# 130807_AriloRX_FINAL_LOGO.net
KiCad netlist of a schematic drawn in EAGLE
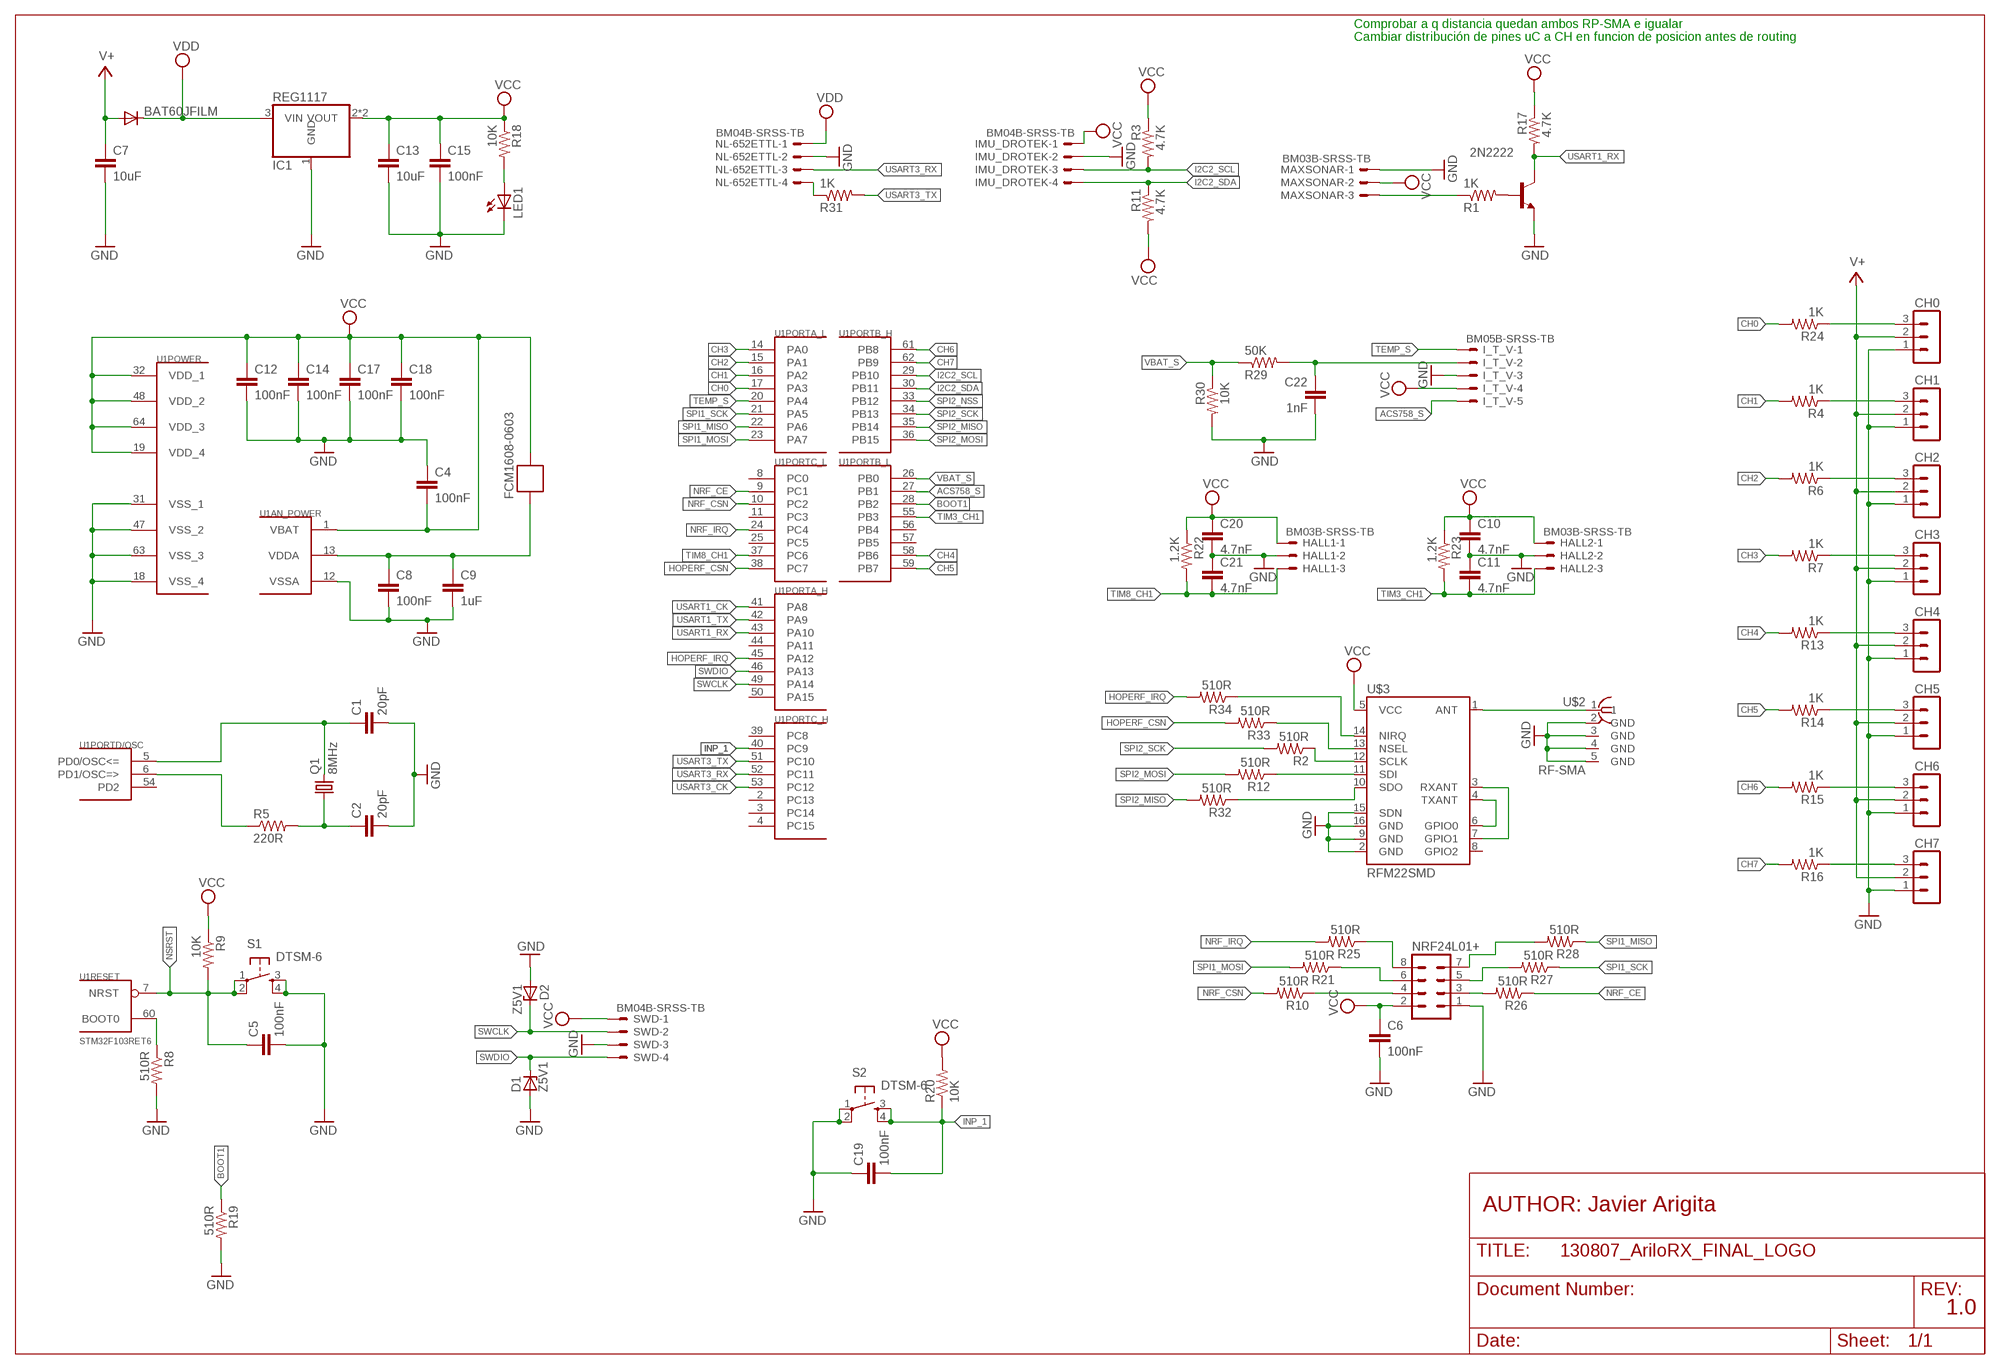
[diagram p0: schematic, sheet 1]

(export (version "E")
  (design (tool "Eeschema 10.0.6"))
  (components
    (comp (ref "2N2222")
      (value "MMBT2222ALT1-NPN-SOT23-BEC")
      (footprint "eagle-import:SOT23-BEC")
      (libsource (lib "eagle-import") (part "-NPN-SOT23-BECMMBT2222ALT1"))
    )
    (comp (ref "BAT60JFILM")
      (value "DIODE-SOD323-R")
      (footprint "eagle-import:SOD323-R")
      (libsource (lib "eagle-import") (part "DIODE-SOD323-R"))
    )
    (comp (ref "C1")
      (value "20pF")
      (footprint "eagle-import:C0805")
      (libsource (lib "eagle-import") (part "C-EUC0805"))
    )
    (comp (ref "C2")
      (value "20pF")
      (footprint "eagle-import:C0805")
      (libsource (lib "eagle-import") (part "C-EUC0805"))
    )
    (comp (ref "C4")
      (value "100nF")
      (footprint "eagle-import:C0805")
      (libsource (lib "eagle-import") (part "C-EUC0805"))
    )
    (comp (ref "C5")
      (value "100nF")
      (footprint "eagle-import:C0805")
      (libsource (lib "eagle-import") (part "C-EUC0805"))
    )
    (comp (ref "C6")
      (value "100nF")
      (footprint "eagle-import:C0805")
      (libsource (lib "eagle-import") (part "C-EUC0805"))
    )
    (comp (ref "C7")
      (value "10uF")
      (footprint "eagle-import:C3216")
      (libsource (lib "eagle-import") (part "resistor_C-EUC3216"))
    )
    (comp (ref "C8")
      (value "100nF")
      (footprint "eagle-import:C0805")
      (libsource (lib "eagle-import") (part "C-EUC0805"))
    )
    (comp (ref "C9")
      (value "1uF")
      (footprint "eagle-import:C3216")
      (libsource (lib "eagle-import") (part "resistor_C-EUC3216"))
    )
    (comp (ref "C10")
      (value "4.7nF")
      (footprint "eagle-import:C0805")
      (libsource (lib "eagle-import") (part "C-EUC0805"))
    )
    (comp (ref "C11")
      (value "4.7nF")
      (footprint "eagle-import:C0805")
      (libsource (lib "eagle-import") (part "C-EUC0805"))
    )
    (comp (ref "C12")
      (value "100nF")
      (footprint "eagle-import:C0805")
      (libsource (lib "eagle-import") (part "C-EUC0805"))
    )
    (comp (ref "C13")
      (value "10uF")
      (footprint "eagle-import:C3216")
      (libsource (lib "eagle-import") (part "resistor_C-EUC3216"))
    )
    (comp (ref "C14")
      (value "100nF")
      (footprint "eagle-import:C0805")
      (libsource (lib "eagle-import") (part "C-EUC0805"))
    )
    (comp (ref "C15")
      (value "100nF")
      (footprint "eagle-import:C0805")
      (libsource (lib "eagle-import") (part "C-EUC0805"))
    )
    (comp (ref "C17")
      (value "100nF")
      (footprint "eagle-import:C0805")
      (libsource (lib "eagle-import") (part "C-EUC0805"))
    )
    (comp (ref "C18")
      (value "100nF")
      (footprint "eagle-import:C0805")
      (libsource (lib "eagle-import") (part "C-EUC0805"))
    )
    (comp (ref "C19")
      (value "100nF")
      (footprint "eagle-import:C0805")
      (libsource (lib "eagle-import") (part "C-EUC0805"))
    )
    (comp (ref "C20")
      (value "4.7nF")
      (footprint "eagle-import:C0805")
      (libsource (lib "eagle-import") (part "C-EUC0805"))
    )
    (comp (ref "C21")
      (value "4.7nF")
      (footprint "eagle-import:C0805")
      (libsource (lib "eagle-import") (part "C-EUC0805"))
    )
    (comp (ref "C22")
      (value "1nF")
      (footprint "eagle-import:C0805")
      (libsource (lib "eagle-import") (part "C-EUC0805"))
    )
    (comp (ref "CH0")
      (value "MA03-1")
      (footprint "eagle-import:MA03-1")
      (libsource (lib "eagle-import") (part "MA03-1"))
    )
    (comp (ref "CH1")
      (value "MA03-1")
      (footprint "eagle-import:MA03-1")
      (libsource (lib "eagle-import") (part "MA03-1"))
    )
    (comp (ref "CH2")
      (value "MA03-1")
      (footprint "eagle-import:MA03-1")
      (libsource (lib "eagle-import") (part "MA03-1"))
    )
    (comp (ref "CH3")
      (value "MA03-1")
      (footprint "eagle-import:MA03-1")
      (libsource (lib "eagle-import") (part "MA03-1"))
    )
    (comp (ref "CH4")
      (value "MA03-1")
      (footprint "eagle-import:MA03-1")
      (libsource (lib "eagle-import") (part "MA03-1"))
    )
    (comp (ref "CH5")
      (value "MA03-1")
      (footprint "eagle-import:MA03-1")
      (libsource (lib "eagle-import") (part "MA03-1"))
    )
    (comp (ref "CH6")
      (value "MA03-1")
      (footprint "eagle-import:MA03-1")
      (libsource (lib "eagle-import") (part "MA03-1"))
    )
    (comp (ref "CH7")
      (value "MA03-1")
      (footprint "eagle-import:MA03-1")
      (libsource (lib "eagle-import") (part "MA03-1"))
    )
    (comp (ref "D1")
      (value "Z5V1")
      (footprint "eagle-import:SOD80C")
      (libsource (lib "eagle-import") (part "ZENER-DIODESOD80C"))
    )
    (comp (ref "D2")
      (value "Z5V1")
      (footprint "eagle-import:SOD80C")
      (libsource (lib "eagle-import") (part "ZENER-DIODESOD80C"))
    )
    (comp (ref "FCM1608-0603")
      (value "FERRITE-BEAD")
      (footprint "eagle-import:R0603")
      (libsource (lib "eagle-import") (part "FERRITE-BEAD"))
    )
    (comp (ref "HALL1")
      (value "BM03B-SRSS-TB")
      (footprint "eagle-import:BM03B-SRSS-TB")
      (libsource (lib "eagle-import") (part "?M03B-SRSS-TBB"))
    )
    (comp (ref "HALL2")
      (value "BM03B-SRSS-TB")
      (footprint "eagle-import:BM03B-SRSS-TB")
      (libsource (lib "eagle-import") (part "?M03B-SRSS-TBB"))
    )
    (comp (ref "IC1")
      (value "REG1117")
      (footprint "eagle-import:SOT223")
      (libsource (lib "eagle-import") (part "REG1117"))
    )
    (comp (ref "IMU_DROTEK")
      (value "BM04B-SRSS-TB")
      (footprint "eagle-import:BM04B-SRSS-TB")
      (libsource (lib "eagle-import") (part "?M04B-SRSS-TBB"))
    )
    (comp (ref "I_T_V")
      (value "BM05B-SRSS-TB")
      (footprint "eagle-import:BM05B-SRSS-TB")
      (libsource (lib "eagle-import") (part "?M05B-SRSS-TBB"))
    )
    (comp (ref "LED1")
      (value "LED0805")
      (footprint "eagle-import:CHIPLED_0805")
      (libsource (lib "eagle-import") (part "LED0805"))
    )
    (comp (ref "MAXSONAR")
      (value "BM03B-SRSS-TB")
      (footprint "eagle-import:BM03B-SRSS-TB")
      (libsource (lib "eagle-import") (part "?M03B-SRSS-TBB"))
    )
    (comp (ref "NL-652ETTL")
      (value "BM04B-SRSS-TB")
      (footprint "eagle-import:BM04B-SRSS-TB")
      (libsource (lib "eagle-import") (part "?M04B-SRSS-TBB"))
    )
    (comp (ref "NRF24L01+")
      (value "MA04-2")
      (footprint "eagle-import:MA04-2")
      (libsource (lib "eagle-import") (part "MA04-2"))
    )
    (comp (ref "Q1")
      (value "8MHz")
      (footprint "eagle-import:SM49")
      (libsource (lib "eagle-import") (part "CRYSTALSM49"))
    )
    (comp (ref "R1")
      (value "1K")
      (footprint "eagle-import:R0805")
      (libsource (lib "eagle-import") (part "RESISTOR0805"))
    )
    (comp (ref "R2")
      (value "510R")
      (footprint "eagle-import:R0805")
      (libsource (lib "eagle-import") (part "RESISTOR0805"))
    )
    (comp (ref "R3")
      (value "4.7K")
      (footprint "eagle-import:R0805")
      (libsource (lib "eagle-import") (part "RESISTOR0805"))
    )
    (comp (ref "R4")
      (value "1K")
      (footprint "eagle-import:R0805")
      (libsource (lib "eagle-import") (part "RESISTOR0805"))
    )
    (comp (ref "R5")
      (value "220R")
      (footprint "eagle-import:R0805")
      (libsource (lib "eagle-import") (part "RESISTOR0805"))
    )
    (comp (ref "R6")
      (value "1K")
      (footprint "eagle-import:R0805")
      (libsource (lib "eagle-import") (part "RESISTOR0805"))
    )
    (comp (ref "R7")
      (value "1K")
      (footprint "eagle-import:R0805")
      (libsource (lib "eagle-import") (part "RESISTOR0805"))
    )
    (comp (ref "R8")
      (value "510R")
      (footprint "eagle-import:R0805")
      (libsource (lib "eagle-import") (part "RESISTOR0805"))
    )
    (comp (ref "R9")
      (value "10K")
      (footprint "eagle-import:R0805")
      (libsource (lib "eagle-import") (part "RESISTOR0805"))
    )
    (comp (ref "R10")
      (value "510R")
      (footprint "eagle-import:R0805")
      (libsource (lib "eagle-import") (part "RESISTOR0805"))
    )
    (comp (ref "R11")
      (value "4.7K")
      (footprint "eagle-import:R0805")
      (libsource (lib "eagle-import") (part "RESISTOR0805"))
    )
    (comp (ref "R12")
      (value "510R")
      (footprint "eagle-import:R0805")
      (libsource (lib "eagle-import") (part "RESISTOR0805"))
    )
    (comp (ref "R13")
      (value "1K")
      (footprint "eagle-import:R0805")
      (libsource (lib "eagle-import") (part "RESISTOR0805"))
    )
    (comp (ref "R14")
      (value "1K")
      (footprint "eagle-import:R0805")
      (libsource (lib "eagle-import") (part "RESISTOR0805"))
    )
    (comp (ref "R15")
      (value "1K")
      (footprint "eagle-import:R0805")
      (libsource (lib "eagle-import") (part "RESISTOR0805"))
    )
    (comp (ref "R16")
      (value "1K")
      (footprint "eagle-import:R0805")
      (libsource (lib "eagle-import") (part "RESISTOR0805"))
    )
    (comp (ref "R17")
      (value "4.7K")
      (footprint "eagle-import:R0805")
      (libsource (lib "eagle-import") (part "RESISTOR0805"))
    )
    (comp (ref "R18")
      (value "10K")
      (footprint "eagle-import:R0805")
      (libsource (lib "eagle-import") (part "RESISTOR0805"))
    )
    (comp (ref "R19")
      (value "510R")
      (footprint "eagle-import:R0805")
      (libsource (lib "eagle-import") (part "RESISTOR0805"))
    )
    (comp (ref "R20")
      (value "10K")
      (footprint "eagle-import:R0805")
      (libsource (lib "eagle-import") (part "RESISTOR0805"))
    )
    (comp (ref "R21")
      (value "510R")
      (footprint "eagle-import:R0805")
      (libsource (lib "eagle-import") (part "RESISTOR0805"))
    )
    (comp (ref "R22")
      (value "1.2K")
      (footprint "eagle-import:R0805")
      (libsource (lib "eagle-import") (part "RESISTOR0805"))
    )
    (comp (ref "R23")
      (value "1.2K")
      (footprint "eagle-import:R0805")
      (libsource (lib "eagle-import") (part "RESISTOR0805"))
    )
    (comp (ref "R24")
      (value "1K")
      (footprint "eagle-import:R0805")
      (libsource (lib "eagle-import") (part "RESISTOR0805"))
    )
    (comp (ref "R25")
      (value "510R")
      (footprint "eagle-import:R0805")
      (libsource (lib "eagle-import") (part "RESISTOR0805"))
    )
    (comp (ref "R26")
      (value "510R")
      (footprint "eagle-import:R0805")
      (libsource (lib "eagle-import") (part "RESISTOR0805"))
    )
    (comp (ref "R27")
      (value "510R")
      (footprint "eagle-import:R0805")
      (libsource (lib "eagle-import") (part "RESISTOR0805"))
    )
    (comp (ref "R28")
      (value "510R")
      (footprint "eagle-import:R0805")
      (libsource (lib "eagle-import") (part "RESISTOR0805"))
    )
    (comp (ref "R29")
      (value "50K")
      (footprint "eagle-import:R0805")
      (libsource (lib "eagle-import") (part "RESISTOR0805"))
    )
    (comp (ref "R30")
      (value "10K")
      (footprint "eagle-import:R0805")
      (libsource (lib "eagle-import") (part "RESISTOR0805"))
    )
    (comp (ref "R31")
      (value "1K")
      (footprint "eagle-import:R0805")
      (libsource (lib "eagle-import") (part "RESISTOR0805"))
    )
    (comp (ref "R32")
      (value "510R")
      (footprint "eagle-import:R0805")
      (libsource (lib "eagle-import") (part "RESISTOR0805"))
    )
    (comp (ref "R33")
      (value "510R")
      (footprint "eagle-import:R0805")
      (libsource (lib "eagle-import") (part "RESISTOR0805"))
    )
    (comp (ref "R34")
      (value "510R")
      (footprint "eagle-import:R0805")
      (libsource (lib "eagle-import") (part "RESISTOR0805"))
    )
    (comp (ref "S1")
      (value "DTSM-6")
      (footprint "eagle-import:DTSM-6")
      (libsource (lib "eagle-import") (part "DTSM-6"))
    )
    (comp (ref "S2")
      (value "DTSM-6")
      (footprint "eagle-import:DTSM-6")
      (libsource (lib "eagle-import") (part "DTSM-6"))
    )
    (comp (ref "SWD")
      (value "BM04B-SRSS-TB")
      (footprint "eagle-import:BM04B-SRSS-TB")
      (libsource (lib "eagle-import") (part "?M04B-SRSS-TBB"))
    )
    (comp (ref "U$2")
      (value "RF-SMA")
      (footprint "eagle-import:BU-SMA-H")
      (libsource (lib "eagle-import") (part "RF-SMA"))
    )
    (comp (ref "U$3")
      (value "RFM22SMD")
      (footprint "eagle-import:RFM22-XXX-S2")
      (libsource (lib "eagle-import") (part "RFM22SMD"))
    )
    (comp (ref "U1")
      (value "STM32F103RET6")
      (footprint "eagle-import:TQFP64")
      (libsource (lib "eagle-import") (part "STM32F10XRXT6"))
    )
  )
  (nets
    (net (code "1") (name "ACS758_S") (class "Default")
      (node (ref "I_T_V") (pin "5") (pinfunction "S_5") (pintype "passive"))
      (node (ref "U1") (pin "27") (pinfunction "PB1_27") (pintype "bidirectional"))
    )
    (net (code "2") (name "BOOT1") (class "Default")
      (node (ref "R19") (pin "1") (pinfunction "1_1") (pintype "passive"))
      (node (ref "U1") (pin "28") (pinfunction "PB2_28") (pintype "bidirectional"))
    )
    (net (code "3") (name "CH0") (class "Default")
      (node (ref "R24") (pin "2") (pinfunction "2_2") (pintype "passive"))
      (node (ref "U1") (pin "17") (pinfunction "PA3_17") (pintype "bidirectional"))
    )
    (net (code "4") (name "CH1") (class "Default")
      (node (ref "R4") (pin "2") (pinfunction "2_2") (pintype "passive"))
      (node (ref "U1") (pin "16") (pinfunction "PA2_16") (pintype "bidirectional"))
    )
    (net (code "5") (name "CH2") (class "Default")
      (node (ref "R6") (pin "2") (pinfunction "2_2") (pintype "passive"))
      (node (ref "U1") (pin "15") (pinfunction "PA1_15") (pintype "bidirectional"))
    )
    (net (code "6") (name "CH3") (class "Default")
      (node (ref "R7") (pin "2") (pinfunction "2_2") (pintype "passive"))
      (node (ref "U1") (pin "14") (pinfunction "PA0_14") (pintype "bidirectional"))
    )
    (net (code "7") (name "CH4") (class "Default")
      (node (ref "R13") (pin "2") (pinfunction "2_2") (pintype "passive"))
      (node (ref "U1") (pin "58") (pinfunction "PB6_58") (pintype "bidirectional"))
    )
    (net (code "8") (name "CH5") (class "Default")
      (node (ref "R14") (pin "2") (pinfunction "2_2") (pintype "passive"))
      (node (ref "U1") (pin "59") (pinfunction "PB7_59") (pintype "bidirectional"))
    )
    (net (code "9") (name "CH6") (class "Default")
      (node (ref "R15") (pin "2") (pinfunction "2_2") (pintype "passive"))
      (node (ref "U1") (pin "61") (pinfunction "PB8_61") (pintype "bidirectional"))
    )
    (net (code "10") (name "CH7") (class "Default")
      (node (ref "R16") (pin "2") (pinfunction "2_2") (pintype "passive"))
      (node (ref "U1") (pin "62") (pinfunction "PB9_62") (pintype "bidirectional"))
    )
    (net (code "11") (name "GND") (class "Default")
      (node (ref "2N2222") (pin "E") (pinfunction "E_E") (pintype "passive"))
      (node (ref "C1") (pin "2") (pinfunction "2_2") (pintype "passive"))
      (node (ref "C10") (pin "2") (pinfunction "2_2") (pintype "passive"))
      (node (ref "C11") (pin "1") (pinfunction "1_1") (pintype "passive"))
      (node (ref "C12") (pin "2") (pinfunction "2_2") (pintype "passive"))
      (node (ref "C13") (pin "2") (pinfunction "2_2") (pintype "passive"))
      (node (ref "C14") (pin "2") (pinfunction "2_2") (pintype "passive"))
      (node (ref "C15") (pin "2") (pinfunction "2_2") (pintype "passive"))
      (node (ref "C17") (pin "2") (pinfunction "2_2") (pintype "passive"))
      (node (ref "C18") (pin "2") (pinfunction "2_2") (pintype "passive"))
      (node (ref "C19") (pin "1") (pinfunction "1_1") (pintype "passive"))
      (node (ref "C2") (pin "2") (pinfunction "2_2") (pintype "passive"))
      (node (ref "C20") (pin "2") (pinfunction "2_2") (pintype "passive"))
      (node (ref "C21") (pin "1") (pinfunction "1_1") (pintype "passive"))
      (node (ref "C22") (pin "2") (pinfunction "2_2") (pintype "passive"))
      (node (ref "C4") (pin "1") (pinfunction "1_1") (pintype "passive"))
      (node (ref "C5") (pin "2") (pinfunction "2_2") (pintype "passive"))
      (node (ref "C6") (pin "2") (pinfunction "2_2") (pintype "passive"))
      (node (ref "C7") (pin "2") (pinfunction "2_2") (pintype "passive"))
      (node (ref "C8") (pin "2") (pinfunction "2_2") (pintype "passive"))
      (node (ref "C9") (pin "2") (pinfunction "2_2") (pintype "passive"))
      (node (ref "CH0") (pin "1") (pinfunction "1_1") (pintype "passive"))
      (node (ref "CH1") (pin "1") (pinfunction "1_1") (pintype "passive"))
      (node (ref "CH2") (pin "1") (pinfunction "1_1") (pintype "passive"))
      (node (ref "CH3") (pin "1") (pinfunction "1_1") (pintype "passive"))
      (node (ref "CH4") (pin "1") (pinfunction "1_1") (pintype "passive"))
      (node (ref "CH5") (pin "1") (pinfunction "1_1") (pintype "passive"))
      (node (ref "CH6") (pin "1") (pinfunction "1_1") (pintype "passive"))
      (node (ref "CH7") (pin "1") (pinfunction "1_1") (pintype "passive"))
      (node (ref "D1") (pin "A") (pinfunction "A_A") (pintype "passive"))
      (node (ref "D2") (pin "A") (pinfunction "A_A") (pintype "passive"))
      (node (ref "HALL1") (pin "2") (pinfunction "S_2") (pintype "passive"))
      (node (ref "HALL2") (pin "2") (pinfunction "S_2") (pintype "passive"))
      (node (ref "IC1") (pin "1") (pinfunction "GND_1") (pintype "power_in"))
      (node (ref "IMU_DROTEK") (pin "2") (pinfunction "S_2") (pintype "passive"))
      (node (ref "I_T_V") (pin "3") (pinfunction "S_3") (pintype "passive"))
      (node (ref "LED1") (pin "C") (pinfunction "C_C") (pintype "passive"))
      (node (ref "MAXSONAR") (pin "1") (pinfunction "S_1") (pintype "passive"))
      (node (ref "NL-652ETTL") (pin "2") (pinfunction "S_2") (pintype "passive"))
      (node (ref "NRF24L01+") (pin "1") (pinfunction "1_1") (pintype "passive"))
      (node (ref "R19") (pin "2") (pinfunction "2_2") (pintype "passive"))
      (node (ref "R30") (pin "2") (pinfunction "2_2") (pintype "passive"))
      (node (ref "R8") (pin "2") (pinfunction "2_2") (pintype "passive"))
      (node (ref "S1") (pin "3") (pinfunction "3_3") (pintype "passive"))
      (node (ref "S1") (pin "4") (pinfunction "4_4") (pintype "passive"))
      (node (ref "S2") (pin "1") (pinfunction "1_1") (pintype "passive"))
      (node (ref "S2") (pin "2") (pinfunction "2_2") (pintype "passive"))
      (node (ref "SWD") (pin "3") (pinfunction "S_3") (pintype "passive"))
      (node (ref "U$2") (pin "2") (pinfunction "GND_2") (pintype "power_in"))
      (node (ref "U$2") (pin "3") (pinfunction "GND_3") (pintype "bidirectional"))
      (node (ref "U$2") (pin "4") (pinfunction "GND_4") (pintype "bidirectional"))
      (node (ref "U$2") (pin "5") (pinfunction "GND_5") (pintype "bidirectional"))
      (node (ref "U$3") (pin "15") (pinfunction "SDN_15") (pintype "input"))
      (node (ref "U$3") (pin "16") (pinfunction "GND_16") (pintype "power_in"))
      (node (ref "U$3") (pin "2") (pinfunction "GND_2") (pintype "power_in"))
      (node (ref "U$3") (pin "9") (pinfunction "GND_9") (pintype "power_in"))
      (node (ref "U1") (pin "12") (pinfunction "VSSA_12") (pintype "power_in"))
      (node (ref "U1") (pin "18") (pinfunction "VSS_4_18") (pintype "power_in"))
      (node (ref "U1") (pin "31") (pinfunction "VSS_1_31") (pintype "power_in"))
      (node (ref "U1") (pin "47") (pinfunction "VSS_2_47") (pintype "power_in"))
      (node (ref "U1") (pin "63") (pinfunction "VSS_3_63") (pintype "power_in"))
    )
    (net (code "12") (name "HOPERF_CSN") (class "Default")
      (node (ref "R33") (pin "2") (pinfunction "2_2") (pintype "passive"))
      (node (ref "U1") (pin "38") (pinfunction "PC7_38") (pintype "bidirectional"))
    )
    (net (code "13") (name "HOPERF_IRQ") (class "Default")
      (node (ref "R34") (pin "2") (pinfunction "2_2") (pintype "passive"))
      (node (ref "U1") (pin "45") (pinfunction "PA12_45") (pintype "bidirectional"))
    )
    (net (code "14") (name "I2C2_SCL") (class "Default")
      (node (ref "IMU_DROTEK") (pin "3") (pinfunction "S_3") (pintype "passive"))
      (node (ref "R3") (pin "2") (pinfunction "2_2") (pintype "passive"))
      (node (ref "U1") (pin "29") (pinfunction "PB10_29") (pintype "bidirectional"))
    )
    (net (code "15") (name "I2C2_SDA") (class "Default")
      (node (ref "IMU_DROTEK") (pin "4") (pinfunction "S_4") (pintype "passive"))
      (node (ref "R11") (pin "1") (pinfunction "1_1") (pintype "passive"))
      (node (ref "U1") (pin "30") (pinfunction "PB11_30") (pintype "bidirectional"))
    )
    (net (code "16") (name "INP_1") (class "Default")
      (node (ref "C19") (pin "2") (pinfunction "2_2") (pintype "passive"))
      (node (ref "R20") (pin "1") (pinfunction "1_1") (pintype "passive"))
      (node (ref "S2") (pin "3") (pinfunction "3_3") (pintype "passive"))
      (node (ref "S2") (pin "4") (pinfunction "4_4") (pintype "passive"))
      (node (ref "U1") (pin "40") (pinfunction "PC9_40") (pintype "bidirectional"))
    )
    (net (code "17") (name "NRF_CE") (class "Default")
      (node (ref "R26") (pin "1") (pinfunction "1_1") (pintype "passive"))
      (node (ref "U1") (pin "9") (pinfunction "PC1_9") (pintype "bidirectional"))
    )
    (net (code "18") (name "NRF_CSN") (class "Default")
      (node (ref "R10") (pin "2") (pinfunction "2_2") (pintype "passive"))
      (node (ref "U1") (pin "10") (pinfunction "PC2_10") (pintype "bidirectional"))
    )
    (net (code "19") (name "NRF_IRQ") (class "Default")
      (node (ref "R25") (pin "2") (pinfunction "2_2") (pintype "passive"))
      (node (ref "U1") (pin "24") (pinfunction "PC4_24") (pintype "bidirectional"))
    )
    (net (code "20") (name "NSRST") (class "Default")
      (node (ref "C5") (pin "1") (pinfunction "1_1") (pintype "passive"))
      (node (ref "R9") (pin "2") (pinfunction "2_2") (pintype "passive"))
      (node (ref "S1") (pin "1") (pinfunction "1_1") (pintype "passive"))
      (node (ref "S1") (pin "2") (pinfunction "2_2") (pintype "passive"))
      (node (ref "U1") (pin "7") (pinfunction "NRST_7") (pintype "input"))
    )
    (net (code "21") (name "Net-(2N2222-PadB)") (class "Default")
      (node (ref "2N2222") (pin "B") (pinfunction "B_B") (pintype "passive"))
      (node (ref "R1") (pin "2") (pinfunction "2_2") (pintype "passive"))
    )
    (net (code "22") (name "Net-(C2-Pad1)") (class "Default")
      (node (ref "C2") (pin "1") (pinfunction "1_1") (pintype "passive"))
      (node (ref "Q1") (pin "1") (pinfunction "1_1") (pintype "passive"))
      (node (ref "R5") (pin "2") (pinfunction "2_2") (pintype "passive"))
    )
    (net (code "23") (name "Net-(CH0-Pad3)") (class "Default")
      (node (ref "CH0") (pin "3") (pinfunction "3_3") (pintype "passive"))
      (node (ref "R24") (pin "1") (pinfunction "1_1") (pintype "passive"))
    )
    (net (code "24") (name "Net-(CH1-Pad3)") (class "Default")
      (node (ref "CH1") (pin "3") (pinfunction "3_3") (pintype "passive"))
      (node (ref "R4") (pin "1") (pinfunction "1_1") (pintype "passive"))
    )
    (net (code "25") (name "Net-(CH2-Pad3)") (class "Default")
      (node (ref "CH2") (pin "3") (pinfunction "3_3") (pintype "passive"))
      (node (ref "R6") (pin "1") (pinfunction "1_1") (pintype "passive"))
    )
    (net (code "26") (name "Net-(CH3-Pad3)") (class "Default")
      (node (ref "CH3") (pin "3") (pinfunction "3_3") (pintype "passive"))
      (node (ref "R7") (pin "1") (pinfunction "1_1") (pintype "passive"))
    )
    (net (code "27") (name "Net-(CH4-Pad3)") (class "Default")
      (node (ref "CH4") (pin "3") (pinfunction "3_3") (pintype "passive"))
      (node (ref "R13") (pin "1") (pinfunction "1_1") (pintype "passive"))
    )
    (net (code "28") (name "Net-(CH5-Pad3)") (class "Default")
      (node (ref "CH5") (pin "3") (pinfunction "3_3") (pintype "passive"))
      (node (ref "R14") (pin "1") (pinfunction "1_1") (pintype "passive"))
    )
    (net (code "29") (name "Net-(CH6-Pad3)") (class "Default")
      (node (ref "CH6") (pin "3") (pinfunction "3_3") (pintype "passive"))
      (node (ref "R15") (pin "1") (pinfunction "1_1") (pintype "passive"))
    )
    (net (code "30") (name "Net-(CH7-Pad3)") (class "Default")
      (node (ref "CH7") (pin "3") (pinfunction "3_3") (pintype "passive"))
      (node (ref "R16") (pin "1") (pinfunction "1_1") (pintype "passive"))
    )
    (net (code "31") (name "Net-(FCM1608-0603-P$2)") (class "Default")
      (node (ref "C8") (pin "1") (pinfunction "1_1") (pintype "passive"))
      (node (ref "C9") (pin "1") (pinfunction "1_1") (pintype "passive"))
      (node (ref "FCM1608-0603") (pin "2") (pinfunction "P$2_2") (pintype "bidirectional"))
      (node (ref "U1") (pin "13") (pinfunction "VDDA_13") (pintype "power_in"))
    )
    (net (code "32") (name "Net-(I_T_VB-S)") (class "Default")
      (node (ref "C22") (pin "1") (pinfunction "1_1") (pintype "passive"))
      (node (ref "I_T_V") (pin "2") (pinfunction "S_2") (pintype "passive"))
      (node (ref "R29") (pin "2") (pinfunction "2_2") (pintype "passive"))
    )
    (net (code "33") (name "Net-(LED1-PadA)") (class "Default")
      (node (ref "LED1") (pin "A") (pinfunction "A_A") (pintype "passive"))
      (node (ref "R18") (pin "2") (pinfunction "2_2") (pintype "passive"))
    )
    (net (code "34") (name "Net-(MAXSONARC-S)") (class "Default")
      (node (ref "MAXSONAR") (pin "3") (pinfunction "S_3") (pintype "passive"))
      (node (ref "R1") (pin "1") (pinfunction "1_1") (pintype "passive"))
    )
    (net (code "35") (name "Net-(NL-652ETTLD-S)") (class "Default")
      (node (ref "NL-652ETTL") (pin "4") (pinfunction "S_4") (pintype "passive"))
      (node (ref "R31") (pin "1") (pinfunction "1_1") (pintype "passive"))
    )
    (net (code "36") (name "Net-(NRF24L01+-Pad3)") (class "Default")
      (node (ref "NRF24L01+") (pin "3") (pinfunction "3_3") (pintype "passive"))
      (node (ref "R26") (pin "2") (pinfunction "2_2") (pintype "passive"))
    )
    (net (code "37") (name "Net-(NRF24L01+-Pad4)") (class "Default")
      (node (ref "NRF24L01+") (pin "4") (pinfunction "4_4") (pintype "passive"))
      (node (ref "R10") (pin "1") (pinfunction "1_1") (pintype "passive"))
    )
    (net (code "38") (name "Net-(NRF24L01+-Pad5)") (class "Default")
      (node (ref "NRF24L01+") (pin "5") (pinfunction "5_5") (pintype "passive"))
      (node (ref "R27") (pin "2") (pinfunction "2_2") (pintype "passive"))
    )
    (net (code "39") (name "Net-(NRF24L01+-Pad6)") (class "Default")
      (node (ref "NRF24L01+") (pin "6") (pinfunction "6_6") (pintype "passive"))
      (node (ref "R21") (pin "1") (pinfunction "1_1") (pintype "passive"))
    )
    (net (code "40") (name "Net-(NRF24L01+-Pad7)") (class "Default")
      (node (ref "NRF24L01+") (pin "7") (pinfunction "7_7") (pintype "passive"))
      (node (ref "R28") (pin "2") (pinfunction "2_2") (pintype "passive"))
    )
    (net (code "41") (name "Net-(NRF24L01+-Pad8)") (class "Default")
      (node (ref "NRF24L01+") (pin "8") (pinfunction "8_8") (pintype "passive"))
      (node (ref "R25") (pin "1") (pinfunction "1_1") (pintype "passive"))
    )
    (net (code "42") (name "Net-(U$3-ANT)") (class "Default")
      (node (ref "U$2") (pin "1") (pinfunction "1_1") (pintype "passive"))
      (node (ref "U$3") (pin "1") (pinfunction "ANT_1") (pintype "bidirectional"))
    )
    (net (code "43") (name "Net-(U$3-GPIO0)") (class "Default")
      (node (ref "U$3") (pin "4") (pinfunction "TXANT_4") (pintype "input"))
      (node (ref "U$3") (pin "6") (pinfunction "GPIO0_6") (pintype "bidirectional"))
    )
    (net (code "44") (name "Net-(U$3-GPIO1)") (class "Default")
      (node (ref "U$3") (pin "3") (pinfunction "RXANT_3") (pintype "input"))
      (node (ref "U$3") (pin "7") (pinfunction "GPIO1_7") (pintype "bidirectional"))
    )
    (net (code "45") (name "Net-(U$3-NIRQ)") (class "Default")
      (node (ref "R34") (pin "1") (pinfunction "1_1") (pintype "passive"))
      (node (ref "U$3") (pin "14") (pinfunction "NIRQ_14") (pintype "output"))
    )
    (net (code "46") (name "Net-(U$3-NSEL)") (class "Default")
      (node (ref "R33") (pin "1") (pinfunction "1_1") (pintype "passive"))
      (node (ref "U$3") (pin "13") (pinfunction "NSEL_13") (pintype "input"))
    )
    (net (code "47") (name "Net-(U$3-SCLK)") (class "Default")
      (node (ref "R2") (pin "1") (pinfunction "1_1") (pintype "passive"))
      (node (ref "U$3") (pin "12") (pinfunction "SCLK_12") (pintype "input"))
    )
    (net (code "48") (name "Net-(U$3-SDI)") (class "Default")
      (node (ref "R12") (pin "1") (pinfunction "1_1") (pintype "passive"))
      (node (ref "U$3") (pin "11") (pinfunction "SDI_11") (pintype "input"))
    )
    (net (code "49") (name "Net-(U$3-SDO)") (class "Default")
      (node (ref "R32") (pin "1") (pinfunction "1_1") (pintype "passive"))
      (node (ref "U$3") (pin "10") (pinfunction "SDO_10") (pintype "output"))
    )
    (net (code "50") (name "Net-(U1H-PD0{slash}OSC<=)") (class "Default")
      (node (ref "C1") (pin "1") (pinfunction "1_1") (pintype "passive"))
      (node (ref "Q1") (pin "2") (pinfunction "2_2") (pintype "passive"))
      (node (ref "U1") (pin "5") (pinfunction "PD0/OSC<=_5") (pintype "bidirectional"))
    )
    (net (code "51") (name "Net-(U1H-PD1{slash}OSC=>)") (class "Default")
      (node (ref "R5") (pin "1") (pinfunction "1_1") (pintype "passive"))
      (node (ref "U1") (pin "6") (pinfunction "PD1/OSC=>_6") (pintype "bidirectional"))
    )
    (net (code "52") (name "Net-(U1J-BOOT0)") (class "Default")
      (node (ref "R8") (pin "1") (pinfunction "1_1") (pintype "passive"))
      (node (ref "U1") (pin "60") (pinfunction "BOOT0_60") (pintype "input"))
    )
    (net (code "53") (name "SPI1_MISO") (class "Default")
      (node (ref "R28") (pin "1") (pinfunction "1_1") (pintype "passive"))
      (node (ref "U1") (pin "22") (pinfunction "PA6_22") (pintype "bidirectional"))
    )
    (net (code "54") (name "SPI1_MOSI") (class "Default")
      (node (ref "R21") (pin "2") (pinfunction "2_2") (pintype "passive"))
      (node (ref "U1") (pin "23") (pinfunction "PA7_23") (pintype "bidirectional"))
    )
    (net (code "55") (name "SPI1_SCK") (class "Default")
      (node (ref "R27") (pin "1") (pinfunction "1_1") (pintype "passive"))
      (node (ref "U1") (pin "21") (pinfunction "PA5_21") (pintype "bidirectional"))
    )
    (net (code "56") (name "SPI2_MISO") (class "Default")
      (node (ref "R32") (pin "2") (pinfunction "2_2") (pintype "passive"))
      (node (ref "U1") (pin "35") (pinfunction "PB14_35") (pintype "bidirectional"))
    )
    (net (code "57") (name "SPI2_MOSI") (class "Default")
      (node (ref "R12") (pin "2") (pinfunction "2_2") (pintype "passive"))
      (node (ref "U1") (pin "36") (pinfunction "PB15_36") (pintype "bidirectional"))
    )
    (net (code "58") (name "SPI2_NSS") (class "Default")
      (node (ref "U1") (pin "33") (pinfunction "PB12_33") (pintype "bidirectional"))
    )
    (net (code "59") (name "SPI2_SCK") (class "Default")
      (node (ref "R2") (pin "2") (pinfunction "2_2") (pintype "passive"))
      (node (ref "U1") (pin "34") (pinfunction "PB13_34") (pintype "bidirectional"))
    )
    (net (code "60") (name "SWCLK") (class "Default")
      (node (ref "D2") (pin "C") (pinfunction "C_C") (pintype "passive"))
      (node (ref "SWD") (pin "2") (pinfunction "S_2") (pintype "passive"))
      (node (ref "U1") (pin "49") (pinfunction "PA14_49") (pintype "bidirectional"))
    )
    (net (code "61") (name "SWDIO") (class "Default")
      (node (ref "D1") (pin "C") (pinfunction "C_C") (pintype "passive"))
      (node (ref "SWD") (pin "4") (pinfunction "S_4") (pintype "passive"))
      (node (ref "U1") (pin "46") (pinfunction "PA13_46") (pintype "bidirectional"))
    )
    (net (code "62") (name "TEMP_S") (class "Default")
      (node (ref "I_T_V") (pin "1") (pinfunction "S_1") (pintype "passive"))
      (node (ref "U1") (pin "20") (pinfunction "PA4_20") (pintype "bidirectional"))
    )
    (net (code "63") (name "TIM3_CH1") (class "Default")
      (node (ref "C11") (pin "2") (pinfunction "2_2") (pintype "passive"))
      (node (ref "HALL2") (pin "3") (pinfunction "S_3") (pintype "passive"))
      (node (ref "R23") (pin "2") (pinfunction "2_2") (pintype "passive"))
      (node (ref "U1") (pin "55") (pinfunction "PB3_55") (pintype "bidirectional"))
    )
    (net (code "64") (name "TIM8_CH1") (class "Default")
      (node (ref "C21") (pin "2") (pinfunction "2_2") (pintype "passive"))
      (node (ref "HALL1") (pin "3") (pinfunction "S_3") (pintype "passive"))
      (node (ref "R22") (pin "2") (pinfunction "2_2") (pintype "passive"))
      (node (ref "U1") (pin "37") (pinfunction "PC6_37") (pintype "bidirectional"))
    )
    (net (code "65") (name "USART1_CK") (class "Default")
      (node (ref "U1") (pin "41") (pinfunction "PA8_41") (pintype "bidirectional"))
    )
    (net (code "66") (name "USART1_RX") (class "Default")
      (node (ref "2N2222") (pin "C") (pinfunction "C_C") (pintype "passive"))
      (node (ref "R17") (pin "2") (pinfunction "2_2") (pintype "passive"))
      (node (ref "U1") (pin "43") (pinfunction "PA10_43") (pintype "bidirectional"))
    )
    (net (code "67") (name "USART1_TX") (class "Default")
      (node (ref "U1") (pin "42") (pinfunction "PA9_42") (pintype "bidirectional"))
    )
    (net (code "68") (name "USART3_CK") (class "Default")
      (node (ref "U1") (pin "53") (pinfunction "PC12_53") (pintype "bidirectional"))
    )
    (net (code "69") (name "USART3_RX") (class "Default")
      (node (ref "NL-652ETTL") (pin "3") (pinfunction "S_3") (pintype "passive"))
      (node (ref "U1") (pin "52") (pinfunction "PC11_52") (pintype "bidirectional"))
    )
    (net (code "70") (name "USART3_TX") (class "Default")
      (node (ref "R31") (pin "2") (pinfunction "2_2") (pintype "passive"))
      (node (ref "U1") (pin "51") (pinfunction "PC10_51") (pintype "bidirectional"))
    )
    (net (code "71") (name "V+") (class "Default")
      (node (ref "BAT60JFILM") (pin "A") (pinfunction "A_A") (pintype "passive"))
      (node (ref "C7") (pin "1") (pinfunction "1_1") (pintype "passive"))
      (node (ref "CH0") (pin "2") (pinfunction "2_2") (pintype "passive"))
      (node (ref "CH1") (pin "2") (pinfunction "2_2") (pintype "passive"))
      (node (ref "CH2") (pin "2") (pinfunction "2_2") (pintype "passive"))
      (node (ref "CH3") (pin "2") (pinfunction "2_2") (pintype "passive"))
      (node (ref "CH4") (pin "2") (pinfunction "2_2") (pintype "passive"))
      (node (ref "CH5") (pin "2") (pinfunction "2_2") (pintype "passive"))
      (node (ref "CH6") (pin "2") (pinfunction "2_2") (pintype "passive"))
      (node (ref "CH7") (pin "2") (pinfunction "2_2") (pintype "passive"))
    )
    (net (code "72") (name "VBAT_S") (class "Default")
      (node (ref "R29") (pin "1") (pinfunction "1_1") (pintype "passive"))
      (node (ref "R30") (pin "1") (pinfunction "1_1") (pintype "passive"))
      (node (ref "U1") (pin "26") (pinfunction "PB0_26") (pintype "bidirectional"))
    )
    (net (code "73") (name "VCC") (class "Default")
      (node (ref "C10") (pin "1") (pinfunction "1_1") (pintype "passive"))
      (node (ref "C12") (pin "1") (pinfunction "1_1") (pintype "passive"))
      (node (ref "C13") (pin "1") (pinfunction "1_1") (pintype "passive"))
      (node (ref "C14") (pin "1") (pinfunction "1_1") (pintype "passive"))
      (node (ref "C15") (pin "1") (pinfunction "1_1") (pintype "passive"))
      (node (ref "C17") (pin "1") (pinfunction "1_1") (pintype "passive"))
      (node (ref "C18") (pin "1") (pinfunction "1_1") (pintype "passive"))
      (node (ref "C20") (pin "1") (pinfunction "1_1") (pintype "passive"))
      (node (ref "C4") (pin "2") (pinfunction "2_2") (pintype "passive"))
      (node (ref "C6") (pin "1") (pinfunction "1_1") (pintype "passive"))
      (node (ref "FCM1608-0603") (pin "1") (pinfunction "P$1_1") (pintype "bidirectional"))
      (node (ref "HALL1") (pin "1") (pinfunction "S_1") (pintype "passive"))
      (node (ref "HALL2") (pin "1") (pinfunction "S_1") (pintype "passive"))
      (node (ref "IC1") (pin "2") (pinfunction "VOUT_2") (pintype "power_in"))
      (node (ref "IC1") (pin "4") (pinfunction "VOUT_4") (pintype "power_in"))
      (node (ref "IMU_DROTEK") (pin "1") (pinfunction "S_1") (pintype "passive"))
      (node (ref "I_T_V") (pin "4") (pinfunction "S_4") (pintype "passive"))
      (node (ref "MAXSONAR") (pin "2") (pinfunction "S_2") (pintype "passive"))
      (node (ref "NRF24L01+") (pin "2") (pinfunction "2_2") (pintype "passive"))
      (node (ref "R11") (pin "2") (pinfunction "2_2") (pintype "passive"))
      (node (ref "R17") (pin "1") (pinfunction "1_1") (pintype "passive"))
      (node (ref "R18") (pin "1") (pinfunction "1_1") (pintype "passive"))
      (node (ref "R20") (pin "2") (pinfunction "2_2") (pintype "passive"))
      (node (ref "R22") (pin "1") (pinfunction "1_1") (pintype "passive"))
      (node (ref "R23") (pin "1") (pinfunction "1_1") (pintype "passive"))
      (node (ref "R3") (pin "1") (pinfunction "1_1") (pintype "passive"))
      (node (ref "R9") (pin "1") (pinfunction "1_1") (pintype "passive"))
      (node (ref "SWD") (pin "1") (pinfunction "S_1") (pintype "passive"))
      (node (ref "U$3") (pin "5") (pinfunction "VCC_5") (pintype "bidirectional"))
      (node (ref "U1") (pin "1") (pinfunction "VBAT_1") (pintype "power_in"))
      (node (ref "U1") (pin "19") (pinfunction "VDD_4_19") (pintype "power_in"))
      (node (ref "U1") (pin "32") (pinfunction "VDD_1_32") (pintype "power_in"))
      (node (ref "U1") (pin "48") (pinfunction "VDD_2_48") (pintype "power_in"))
      (node (ref "U1") (pin "64") (pinfunction "VDD_3_64") (pintype "power_in"))
    )
    (net (code "74") (name "VDD") (class "Default")
      (node (ref "BAT60JFILM") (pin "C") (pinfunction "C_C") (pintype "passive"))
      (node (ref "IC1") (pin "3") (pinfunction "VIN_3") (pintype "input"))
      (node (ref "NL-652ETTL") (pin "1") (pinfunction "S_1") (pintype "passive"))
    )
    (net (code "75") (name "unconnected-(U$3-GPIO2-Pad8)") (class "Default")
      (node (ref "U$3") (pin "8") (pinfunction "GPIO2_8") (pintype "bidirectional"))
    )
    (net (code "76") (name "unconnected-(U1B-PA11-Pad44)") (class "Default")
      (node (ref "U1") (pin "44") (pinfunction "PA11_44") (pintype "bidirectional"))
    )
    (net (code "77") (name "unconnected-(U1B-PA15-Pad50)") (class "Default")
      (node (ref "U1") (pin "50") (pinfunction "PA15_50") (pintype "bidirectional"))
    )
    (net (code "78") (name "unconnected-(U1E-PB4-Pad56)") (class "Default")
      (node (ref "U1") (pin "56") (pinfunction "PB4_56") (pintype "bidirectional"))
    )
    (net (code "79") (name "unconnected-(U1E-PB5-Pad57)") (class "Default")
      (node (ref "U1") (pin "57") (pinfunction "PB5_57") (pintype "bidirectional"))
    )
    (net (code "80") (name "unconnected-(U1F-PC8-Pad39)") (class "Default")
      (node (ref "U1") (pin "39") (pinfunction "PC8_39") (pintype "bidirectional"))
    )
    (net (code "81") (name "unconnected-(U1F-PC13-Pad2)") (class "Default")
      (node (ref "U1") (pin "2") (pinfunction "PC13_2") (pintype "bidirectional"))
    )
    (net (code "82") (name "unconnected-(U1F-PC14-Pad3)") (class "Default")
      (node (ref "U1") (pin "3") (pinfunction "PC14_3") (pintype "bidirectional"))
    )
    (net (code "83") (name "unconnected-(U1F-PC15-Pad4)") (class "Default")
      (node (ref "U1") (pin "4") (pinfunction "PC15_4") (pintype "bidirectional"))
    )
    (net (code "84") (name "unconnected-(U1G-PC0-Pad8)") (class "Default")
      (node (ref "U1") (pin "8") (pinfunction "PC0_8") (pintype "bidirectional"))
    )
    (net (code "85") (name "unconnected-(U1G-PC3-Pad11)") (class "Default")
      (node (ref "U1") (pin "11") (pinfunction "PC3_11") (pintype "bidirectional"))
    )
    (net (code "86") (name "unconnected-(U1G-PC5-Pad25)") (class "Default")
      (node (ref "U1") (pin "25") (pinfunction "PC5_25") (pintype "bidirectional"))
    )
    (net (code "87") (name "unconnected-(U1H-PD2-Pad54)") (class "Default")
      (node (ref "U1") (pin "54") (pinfunction "PD2_54") (pintype "bidirectional"))
    )
  )
)
